# BMS_AFE_-_Thermistors.net
KiCad netlist of a schematic drawn in Altium Designer
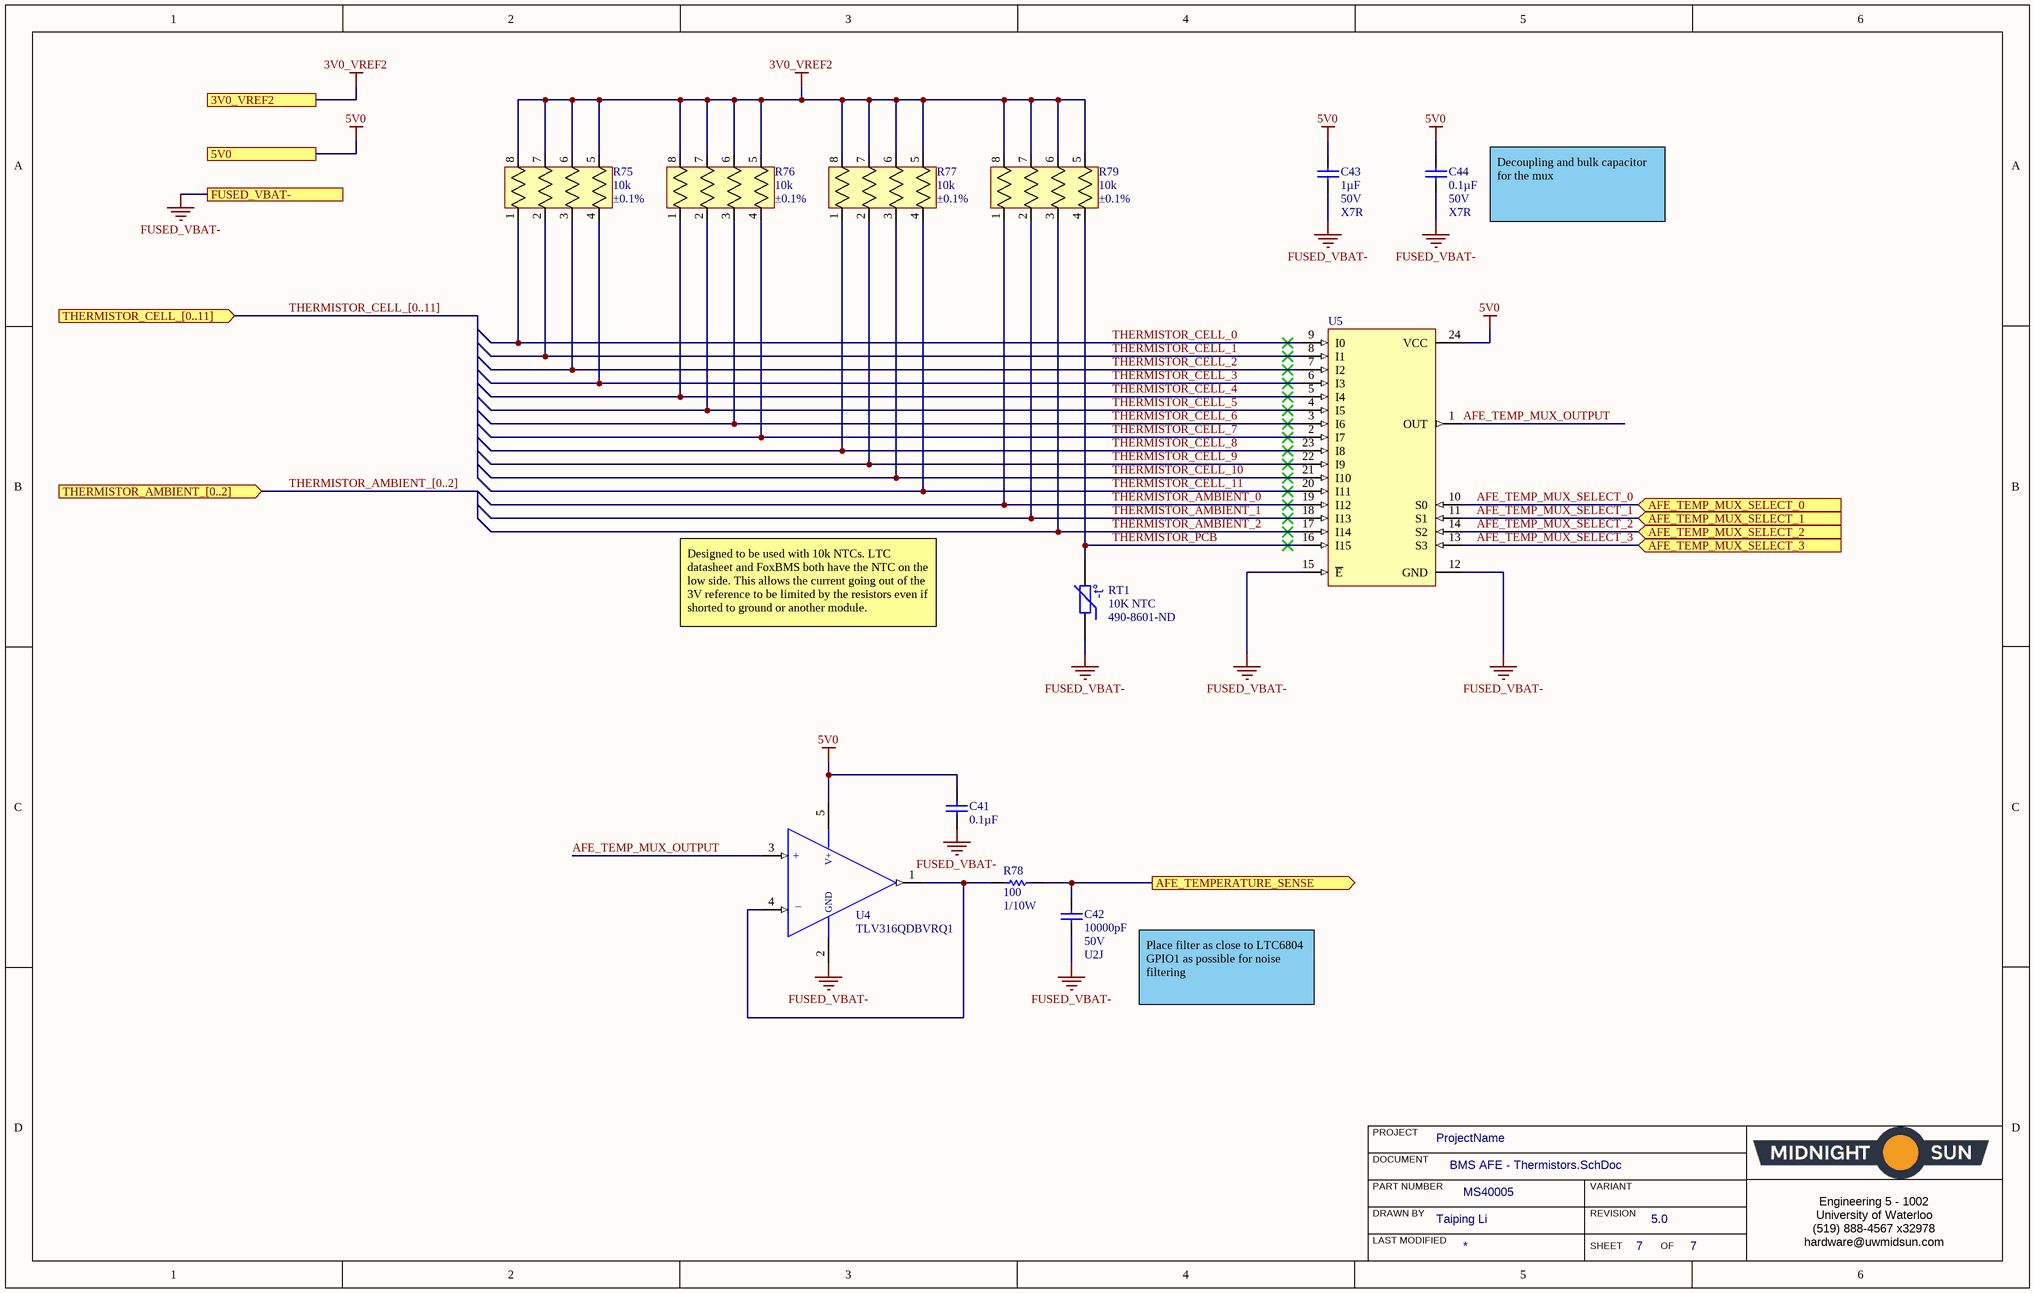
[diagram p0: BMS AFE - Thermistors.SchDoc]

(export (version "E")
  (design (tool "Eeschema 10.0.6"))
  (components
    (comp (ref "C41")
      (value "CAP CER 0.1UF 50V 10% X7R 0603")
      (footprint "CAP, 0603")
      (description "0.10µF ±10% 50V Ceramic Capacitor X7R 0603 (1608 Metric)")
      (fields
        (field (name "TOLERANCE") "±10%")
        (field (name "CAPACITANCE") "0.1µF")
        (field (name "VOLTAGE") "50V")
      )
      (libsource (lib "Schematic Diagrams") (part "CAP CER 0.1UF 50V 10% X7R 0603"))
    )
    (comp (ref "C42")
      (value "CAP CER 10nF 50V 5% X7R 0603")
      (footprint "CAP, 0603")
      (description "10000pF ±5% 50V Ceramic Capacitor U2J 0603 (1608 Metric)")
      (fields
        (field (name "TOLERANCE") "±5%")
        (field (name "CAPACITANCE") "10000pF")
        (field (name "VOLTAGE") "50V")
        (field (name "TEMPERATURE COEFFICIENT") "U2J")
      )
      (libsource (lib "Schematic Diagrams") (part "CAP CER 10nF 50V 5% X7R 0603"))
    )
    (comp (ref "C43")
      (value "CAP CER 1UF 50V 10% X7R 0603")
      (footprint "CAP, 0603")
      (description "1µF ±10% 50V Ceramic Capacitor X7R 0603 (1608 Metric)")
      (fields
        (field (name "TOLERANCE") "±10%")
        (field (name "CAPACITANCE") "1µF")
        (field (name "VOLTAGE") "50V")
        (field (name "TEMPERATURE COEFFICIENT") "X7R")
      )
      (libsource (lib "Schematic Diagrams") (part "CAP CER 1UF 50V 10% X7R 0603"))
    )
    (comp (ref "C44")
      (value "CAP CER 0.1UF 50V 10% X7R 0603")
      (footprint "CAP, 0603")
      (description "0.10µF ±10% 50V Ceramic Capacitor X7R 0603 (1608 Metric)")
      (fields
        (field (name "TOLERANCE") "±10%")
        (field (name "CAPACITANCE") "0.1µF")
        (field (name "VOLTAGE") "50V")
        (field (name "TEMPERATURE COEFFICIENT") "X7R")
      )
      (libsource (lib "Schematic Diagrams") (part "CAP CER 0.1UF 50V 10% X7R 0603"))
    )
    (comp (ref "R75")
      (value "RES ARRAY 10K OHM 0.1% 4RES 1206")
      (footprint "RES ARRAY 4RES 1206")
      (fields
        (field (name "MANUFACTURER") "Vishay Beyschlag")
        (field (name "MANUFACTURER PART NUMBER") "ACASA1002S1002P100")
        (field (name "RESISTANCE (OHMS)") "10k")
        (field (name "TOLERANCE") "±0.1%")
      )
      (libsource (lib "Schematic Diagrams") (part "RES ARRAY 10K OHM 0.1% 4RES 1206"))
    )
    (comp (ref "R76")
      (value "RES ARRAY 10K OHM 0.1% 4RES 1206")
      (footprint "RES ARRAY 4RES 1206")
      (fields
        (field (name "MANUFACTURER") "Vishay Beyschlag")
        (field (name "MANUFACTURER PART NUMBER") "ACASA1002S1002P100")
        (field (name "RESISTANCE (OHMS)") "10k")
        (field (name "TOLERANCE") "±0.1%")
      )
      (libsource (lib "Schematic Diagrams") (part "RES ARRAY 10K OHM 0.1% 4RES 1206"))
    )
    (comp (ref "R77")
      (value "RES ARRAY 10K OHM 0.1% 4RES 1206")
      (footprint "RES ARRAY 4RES 1206")
      (fields
        (field (name "MANUFACTURER") "Vishay Beyschlag")
        (field (name "MANUFACTURER PART NUMBER") "ACASA1002S1002P100")
        (field (name "RESISTANCE (OHMS)") "10k")
        (field (name "TOLERANCE") "±0.1%")
      )
      (libsource (lib "Schematic Diagrams") (part "RES ARRAY 10K OHM 0.1% 4RES 1206"))
    )
    (comp (ref "R78")
      (value "RES 100 OHM 1% 1/10W 0603")
      (footprint "RES, 0603")
      (description "100 Ohm ±1% 0.1W, 1/10W Chip Resistor 0603 (1608 Metric) Moisture Resistant Thick Film")
      (fields
        (field (name "TOLERANCE") "±1%")
        (field (name "RESISTANCE") "100")
        (field (name "POWER") "1/10W")
      )
      (libsource (lib "Schematic Diagrams") (part "RES 100 OHM 1% 1/10W 0603"))
    )
    (comp (ref "R79")
      (value "RES ARRAY 10K OHM 0.1% 4RES 1206")
      (footprint "RES ARRAY 4RES 1206")
      (fields
        (field (name "MANUFACTURER") "Vishay Beyschlag")
        (field (name "MANUFACTURER PART NUMBER") "ACASA1002S1002P100")
        (field (name "RESISTANCE (OHMS)") "10k")
        (field (name "TOLERANCE") "±0.1%")
      )
      (libsource (lib "Schematic Diagrams") (part "RES ARRAY 10K OHM 0.1% 4RES 1206"))
    )
    (comp (ref "RT1")
      (value "10K NTC")
      (footprint "NTC THERMISTOR BEAD")
      (description "NTC Thermistor 10k Bead")
      (fields
        (field (name "MANUFACTURER") "Murata Electronics North America")
        (field (name "MANUFACTURER PART NUMBER") "NXRT15XH103FA1B030")
        (field (name "SUPPLIER PART NUMBER 1") "490-8601-ND")
      )
      (libsource (lib "Schematic Diagrams") (part "NTC THERMISTOR 10K 1% BEAD"))
    )
    (comp (ref "U4")
      (value "IC OP AMP GEN PURPOSE RR 10MHZ SOT-23-5")
      (footprint "IC OP AMP GP RR 10MHZ SOT-23-5")
      (description "General Purpose Amplifier 1 Circuit Rail-to-Rail SOT-23-5")
      (fields (field (name "MANUFACTURER PART NUMBER 1") "TLV316QDBVRQ1"))
      (libsource (lib "Schematic Diagrams") (part "IC OP AMP GEN PURPOSE RR 10MHZ SOT-23-5"))
    )
    (comp (ref "U5")
      (value "IC MUX/DEMUX 1X16 24SSOP")
      (footprint "SOP127P1030X265-24N")
      (description "1 Circuit IC Switch 16:1 160 Ohm 24-SOIC")
      (fields
        (field (name "MANUFACTURER") "Texas Instruments")
        (field (name "MANUFACTURER PART NUMBER") "CD74HC4067M96")
      )
      (libsource (lib "Schematic Diagrams") (part "IC MUX/DEMUX 1X16 24SSOP"))
    )
  )
  (nets
    (net (code "1") (name "/AFE_TEMPERATURE_SENSE") (class "Default")
      (node (ref "C42") (pin "1") (pinfunction "1_1") (pintype "passive"))
      (node (ref "R78") (pin "2") (pinfunction "2_2") (pintype "passive"))
    )
    (net (code "2") (name "/AFE_TEMP_MUX_OUTPUT") (class "Default")
      (node (ref "U4") (pin "3") (pinfunction "+IN_3") (pintype "input"))
      (node (ref "U5") (pin "1") (pinfunction "OUT_1") (pintype "output"))
    )
    (net (code "3") (name "/AFE_TEMP_MUX_SELECT_0") (class "Default")
      (node (ref "U5") (pin "10") (pinfunction "S0_10") (pintype "input"))
    )
    (net (code "4") (name "/AFE_TEMP_MUX_SELECT_1") (class "Default")
      (node (ref "U5") (pin "11") (pinfunction "S1_11") (pintype "input"))
    )
    (net (code "5") (name "/AFE_TEMP_MUX_SELECT_2") (class "Default")
      (node (ref "U5") (pin "14") (pinfunction "S2_14") (pintype "input"))
    )
    (net (code "6") (name "/AFE_TEMP_MUX_SELECT_3") (class "Default")
      (node (ref "U5") (pin "13") (pinfunction "S3_13") (pintype "input"))
    )
    (net (code "7") (name "/THERMISTOR_AMBIENT_0") (class "Default")
      (node (ref "R79") (pin "1") (pinfunction "1_1") (pintype "passive"))
      (node (ref "U5") (pin "19") (pinfunction "I12_19") (pintype "input"))
    )
    (net (code "8") (name "/THERMISTOR_AMBIENT_1") (class "Default")
      (node (ref "R79") (pin "2") (pinfunction "2_2") (pintype "passive"))
      (node (ref "U5") (pin "18") (pinfunction "I13_18") (pintype "input"))
    )
    (net (code "9") (name "/THERMISTOR_AMBIENT_2") (class "Default")
      (node (ref "R79") (pin "3") (pinfunction "3_3") (pintype "passive"))
      (node (ref "U5") (pin "17") (pinfunction "I14_17") (pintype "input"))
    )
    (net (code "11") (name "/THERMISTOR_CELL_0") (class "Default")
      (node (ref "R75") (pin "1") (pinfunction "1_1") (pintype "passive"))
      (node (ref "U5") (pin "9") (pinfunction "I0_9") (pintype "input"))
    )
    (net (code "12") (name "/THERMISTOR_CELL_1") (class "Default")
      (node (ref "R75") (pin "2") (pinfunction "2_2") (pintype "passive"))
      (node (ref "U5") (pin "8") (pinfunction "I1_8") (pintype "input"))
    )
    (net (code "13") (name "/THERMISTOR_CELL_2") (class "Default")
      (node (ref "R75") (pin "3") (pinfunction "3_3") (pintype "passive"))
      (node (ref "U5") (pin "7") (pinfunction "I2_7") (pintype "input"))
    )
    (net (code "14") (name "/THERMISTOR_CELL_3") (class "Default")
      (node (ref "R75") (pin "4") (pinfunction "4_4") (pintype "passive"))
      (node (ref "U5") (pin "6") (pinfunction "I3_6") (pintype "input"))
    )
    (net (code "15") (name "/THERMISTOR_CELL_4") (class "Default")
      (node (ref "R76") (pin "1") (pinfunction "1_1") (pintype "passive"))
      (node (ref "U5") (pin "5") (pinfunction "I4_5") (pintype "input"))
    )
    (net (code "16") (name "/THERMISTOR_CELL_5") (class "Default")
      (node (ref "R76") (pin "2") (pinfunction "2_2") (pintype "passive"))
      (node (ref "U5") (pin "4") (pinfunction "I5_4") (pintype "input"))
    )
    (net (code "17") (name "/THERMISTOR_CELL_6") (class "Default")
      (node (ref "R76") (pin "3") (pinfunction "3_3") (pintype "passive"))
      (node (ref "U5") (pin "3") (pinfunction "I6_3") (pintype "input"))
    )
    (net (code "18") (name "/THERMISTOR_CELL_7") (class "Default")
      (node (ref "R76") (pin "4") (pinfunction "4_4") (pintype "passive"))
      (node (ref "U5") (pin "2") (pinfunction "I7_2") (pintype "input"))
    )
    (net (code "19") (name "/THERMISTOR_CELL_8") (class "Default")
      (node (ref "R77") (pin "1") (pinfunction "1_1") (pintype "passive"))
      (node (ref "U5") (pin "23") (pinfunction "I8_23") (pintype "input"))
    )
    (net (code "20") (name "/THERMISTOR_CELL_9") (class "Default")
      (node (ref "R77") (pin "2") (pinfunction "2_2") (pintype "passive"))
      (node (ref "U5") (pin "22") (pinfunction "I9_22") (pintype "input"))
    )
    (net (code "21") (name "/THERMISTOR_CELL_10") (class "Default")
      (node (ref "R77") (pin "3") (pinfunction "3_3") (pintype "passive"))
      (node (ref "U5") (pin "21") (pinfunction "I10_21") (pintype "input"))
    )
    (net (code "22") (name "/THERMISTOR_CELL_11") (class "Default")
      (node (ref "R77") (pin "4") (pinfunction "4_4") (pintype "passive"))
      (node (ref "U5") (pin "20") (pinfunction "I11_20") (pintype "input"))
    )
    (net (code "24") (name "/THERMISTOR_PCB") (class "Default")
      (node (ref "R79") (pin "4") (pinfunction "4_4") (pintype "passive"))
      (node (ref "RT1") (pin "2") (pinfunction "2_2") (pintype "passive"))
      (node (ref "U5") (pin "16") (pinfunction "I15_16") (pintype "input"))
    )
    (net (code "25") (name "3V0_VREF2") (class "Default")
      (node (ref "R75") (pin "5") (pinfunction "5_5") (pintype "passive"))
      (node (ref "R75") (pin "6") (pinfunction "6_6") (pintype "passive"))
      (node (ref "R75") (pin "7") (pinfunction "7_7") (pintype "passive"))
      (node (ref "R75") (pin "8") (pinfunction "8_8") (pintype "passive"))
      (node (ref "R76") (pin "5") (pinfunction "5_5") (pintype "passive"))
      (node (ref "R76") (pin "6") (pinfunction "6_6") (pintype "passive"))
      (node (ref "R76") (pin "7") (pinfunction "7_7") (pintype "passive"))
      (node (ref "R76") (pin "8") (pinfunction "8_8") (pintype "passive"))
      (node (ref "R77") (pin "5") (pinfunction "5_5") (pintype "passive"))
      (node (ref "R77") (pin "6") (pinfunction "6_6") (pintype "passive"))
      (node (ref "R77") (pin "7") (pinfunction "7_7") (pintype "passive"))
      (node (ref "R77") (pin "8") (pinfunction "8_8") (pintype "passive"))
      (node (ref "R79") (pin "5") (pinfunction "5_5") (pintype "passive"))
      (node (ref "R79") (pin "6") (pinfunction "6_6") (pintype "passive"))
      (node (ref "R79") (pin "7") (pinfunction "7_7") (pintype "passive"))
      (node (ref "R79") (pin "8") (pinfunction "8_8") (pintype "passive"))
    )
    (net (code "26") (name "5V0") (class "Default")
      (node (ref "C41") (pin "1") (pinfunction "1_1") (pintype "passive"))
      (node (ref "C43") (pin "1") (pinfunction "1_1") (pintype "passive"))
      (node (ref "C44") (pin "1") (pinfunction "1_1") (pintype "passive"))
      (node (ref "U4") (pin "5") (pinfunction "VDD_5") (pintype "power_in"))
      (node (ref "U5") (pin "24") (pinfunction "VCC_24") (pintype "power_in"))
    )
    (net (code "27") (name "FUSED_VBAT-") (class "Default")
      (node (ref "C41") (pin "2") (pinfunction "2_2") (pintype "passive"))
      (node (ref "C42") (pin "2") (pinfunction "2_2") (pintype "passive"))
      (node (ref "C43") (pin "2") (pinfunction "2_2") (pintype "passive"))
      (node (ref "C44") (pin "2") (pinfunction "2_2") (pintype "passive"))
      (node (ref "RT1") (pin "1") (pinfunction "1_1") (pintype "passive"))
      (node (ref "U4") (pin "2") (pinfunction "VSS_2") (pintype "power_in"))
      (node (ref "U5") (pin "12") (pinfunction "GND_12") (pintype "power_in"))
      (node (ref "U5") (pin "15") (pinfunction "~{E}_15") (pintype "input"))
    )
    (net (code "28") (name "Net-(U4--IN)") (class "Default")
      (node (ref "R78") (pin "1") (pinfunction "1_1") (pintype "passive"))
      (node (ref "U4") (pin "1") (pinfunction "OUTPUT_1") (pintype "output"))
      (node (ref "U4") (pin "4") (pinfunction "-IN_4") (pintype "input"))
    )
  )
)
